# 1_Main_copy.net
KiCad netlist of a schematic drawn in Altium Designer
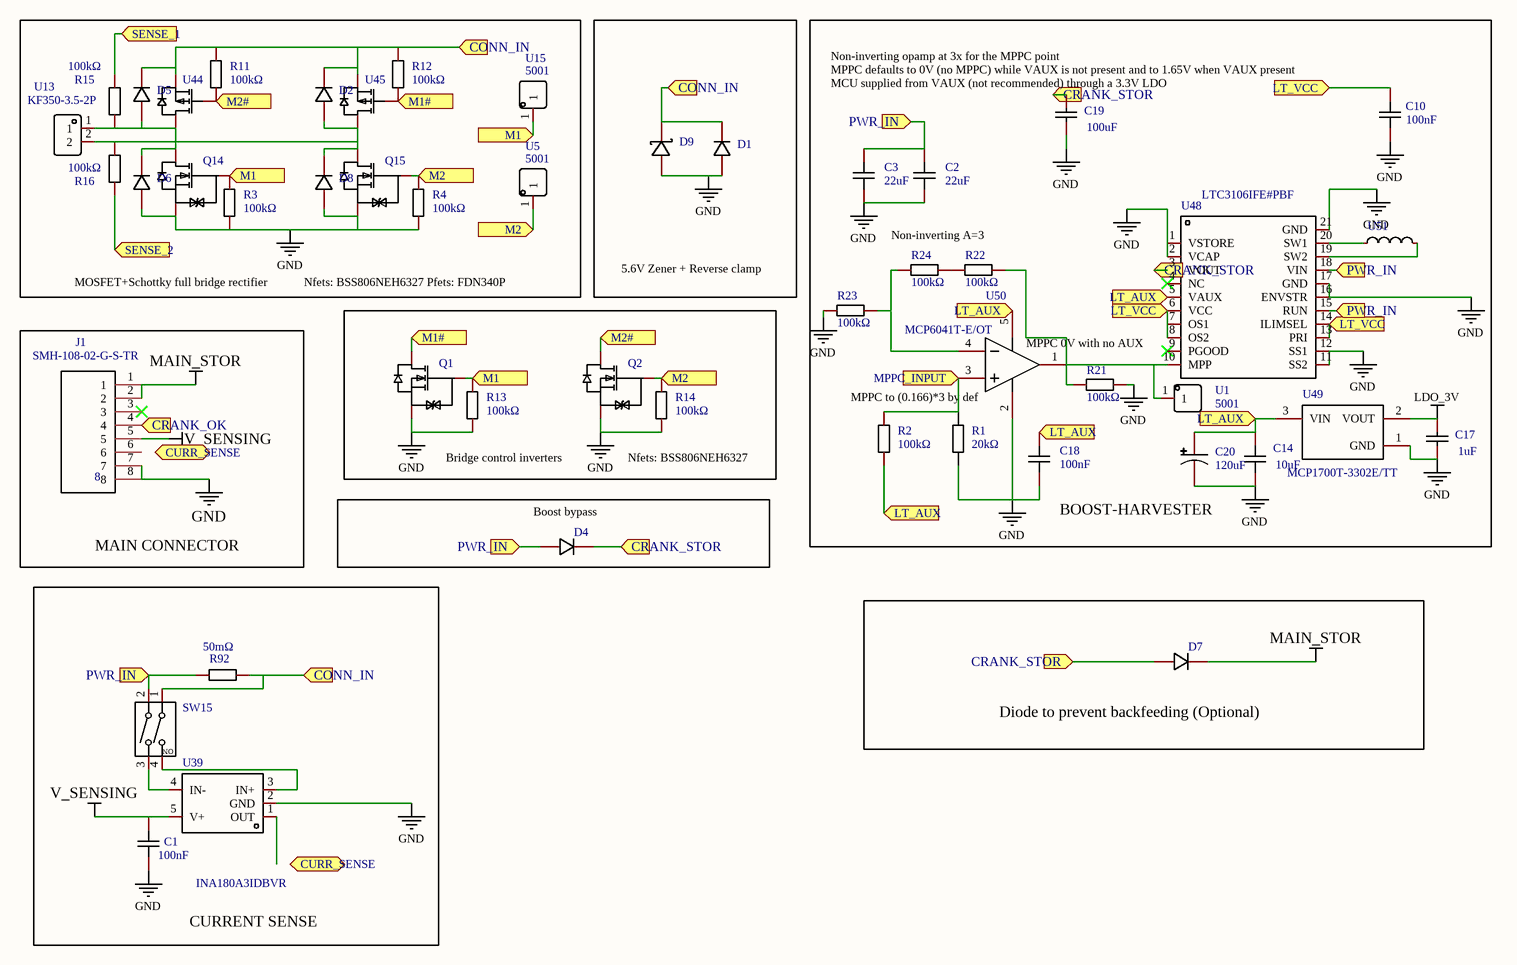
[diagram p0: 1_Main copy.schdoc]

(export (version "E")
  (design (tool "Eeschema 10.0.6"))
  (components
    (comp (ref "C1")
      (value "100nF")
      (fields
        (field (name "NAME") "100nF")
        (field (name "MANUFACTURER") "YAGEO")
        (field (name "MANUFACTURER PART") "CC0603KRX7R9BB104")
      )
      (libsource (lib "altium-import") (part "root_1_CC0603KRX7R9BB104_"))
    )
    (comp (ref "C2")
      (value "22uF")
      (fields
        (field (name "MANUFACTURER") "SAMSUNG(三星)")
        (field (name "MANUFACTURER PART") "CL21A226MAQNNNE")
        (field (name "TOLERANCE") "±20%")
      )
      (libsource (lib "altium-import") (part "root_1_mirrored_CL21A226MAQNNNE_C45783_"))
    )
    (comp (ref "C3")
      (value "22uF")
      (fields
        (field (name "MANUFACTURER") "SAMSUNG(三星)")
        (field (name "MANUFACTURER PART") "CL21A226MAQNNNE")
        (field (name "TOLERANCE") "±20%")
      )
      (libsource (lib "altium-import") (part "root_1_mirrored_CL21A226MAQNNNE_C45783_"))
    )
    (comp (ref "C10")
      (value "100nF")
      (fields
        (field (name "NAME") "100nF")
        (field (name "MANUFACTURER") "YAGEO")
        (field (name "MANUFACTURER PART") "CC0603KRX7R9BB104")
      )
      (libsource (lib "altium-import") (part "root_3_CC0603KRX7R9BB104_"))
    )
    (comp (ref "C14")
      (value "10uF")
      (fields
        (field (name "MANUFACTURER") "SAMSUNG(三星)")
        (field (name "MANUFACTURER PART") "CL10A106MA8NRNC")
        (field (name "TOLERANCE") "±20%")
      )
      (libsource (lib "altium-import") (part "root_1_CL10A106MA8NRNC_"))
    )
    (comp (ref "C17")
      (value "1uF")
      (fields
        (field (name "MANUFACTURER") "SAMSUNG(三星)")
        (field (name "MANUFACTURER PART") "CL10A105KB8NNNC")
        (field (name "TOLERANCE") "±10%")
      )
      (libsource (lib "altium-import") (part "root_1_CL10A105KB8NNNC_"))
    )
    (comp (ref "C18")
      (value "100nF")
      (fields
        (field (name "NAME") "100nF")
        (field (name "MANUFACTURER") "YAGEO")
        (field (name "MANUFACTURER PART") "CC0603KRX7R9BB104")
      )
      (libsource (lib "altium-import") (part "root_1_CC0603KRX7R9BB104_"))
    )
    (comp (ref "C19")
      (value "100uF")
      (fields
        (field (name "MANUFACTURER") "SAMSUNG(三星)")
        (field (name "MANUFACTURER PART") "CL32A107MQVNNNE")
        (field (name "TOLERANCE") "±20%")
      )
      (libsource (lib "altium-import") (part "root_1_CL32A107MQVNNNE_"))
    )
    (comp (ref "C20")
      (value "120uF")
      (fields
        (field (name "MANUFACTURER") "PANASONIC(松下)")
        (field (name "MANUFACTURER PART") "EEEFK1A121SR")
        (field (name "TOLERANCE") "±20%")
      )
      (libsource (lib "altium-import") (part "root_0_EEEFK1A121SR_"))
    )
    (comp (ref "D1")
      (value "STPS1L30U")
      (description "Reverse Voltage (Vr):30V Average Rectified Current (Io):1A Forward Voltage (Vf@If):395mV@1A")
      (fields (field (name "MANUFACTURER") "ST(意法半导体)"))
      (libsource (lib "altium-import") (part "root_3_STPS1L30U_"))
    )
    (comp (ref "D2")
      (value "STPS1L30U")
      (description "Reverse Voltage (Vr):30V Average Rectified Current (Io):1A Forward Voltage (Vf@If):395mV@1A")
      (fields (field (name "MANUFACTURER") "ST(意法半导体)"))
      (libsource (lib "altium-import") (part "root_3_STPS1L30U_"))
    )
    (comp (ref "D4")
      (value "STPS1L30U")
      (description "Reverse Voltage (Vr):30V Average Rectified Current (Io):1A Forward Voltage (Vf@If):395mV@1A")
      (fields (field (name "MANUFACTURER") "ST(意法半导体)"))
      (libsource (lib "altium-import") (part "root_2_STPS1L30U_"))
    )
    (comp (ref "D5")
      (value "STPS1L30U")
      (description "Reverse Voltage (Vr):30V Average Rectified Current (Io):1A Forward Voltage (Vf@If):395mV@1A")
      (fields (field (name "MANUFACTURER") "ST(意法半导体)"))
      (libsource (lib "altium-import") (part "root_3_STPS1L30U_"))
    )
    (comp (ref "D6")
      (value "STPS1L30U")
      (description "Reverse Voltage (Vr):30V Average Rectified Current (Io):1A Forward Voltage (Vf@If):395mV@1A")
      (fields (field (name "MANUFACTURER") "ST(意法半导体)"))
      (libsource (lib "altium-import") (part "root_3_STPS1L30U_"))
    )
    (comp (ref "D7")
      (value "STPS1L30U")
      (description "Reverse Voltage (Vr):30V Average Rectified Current (Io):1A Forward Voltage (Vf@If):395mV@1A")
      (fields (field (name "MANUFACTURER") "ST(意法半导体)"))
      (libsource (lib "altium-import") (part "root_2_STPS1L30U_"))
    )
    (comp (ref "D8")
      (value "STPS1L30U")
      (description "Reverse Voltage (Vr):30V Average Rectified Current (Io):1A Forward Voltage (Vf@If):395mV@1A")
      (fields (field (name "MANUFACTURER") "ST(意法半导体)"))
      (libsource (lib "altium-import") (part "root_3_STPS1L30U_"))
    )
    (comp (ref "D9")
      (value "SMAZ5V6-13-F")
      (fields (field (name "MANUFACTURER") "DIODES(美台)") (field (name "TOLERANCE") "±5%"))
      (libsource (lib "altium-import") (part "root_3_SMAZ5V6-13-F_"))
    )
    (comp (ref "J1")
      (value "SMH-108-02-G-S-TR")
      (fields (field (name "NAME") "SMH-108-02-G-S-TR") (field (name "NAME_1") "8"))
      (libsource (lib "altium-import") (part "root_0_SMH-108-02-G-S-TR_"))
    )
    (comp (ref "Q1")
      (value "BSS806NEH6327")
      (fields (field (name "MANUFACTURER") "Infineon(英飞凌)"))
      (libsource (lib "altium-import") (part "root_0_mirrored_BSS806NEH6327_"))
    )
    (comp (ref "Q2")
      (value "BSS806NEH6327")
      (fields (field (name "MANUFACTURER") "Infineon(英飞凌)"))
      (libsource (lib "altium-import") (part "root_0_mirrored_BSS806NEH6327_"))
    )
    (comp (ref "Q14")
      (value "BSS806NEH6327")
      (fields (field (name "MANUFACTURER") "Infineon(英飞凌)"))
      (libsource (lib "altium-import") (part "root_0_mirrored_BSS806NEH6327_"))
    )
    (comp (ref "Q15")
      (value "BSS806NEH6327")
      (fields (field (name "MANUFACTURER") "Infineon(英飞凌)"))
      (libsource (lib "altium-import") (part "root_0_mirrored_BSS806NEH6327_"))
    )
    (comp (ref "R1")
      (value "20kΩ")
      (fields
        (field (name "NAME") "20kΩ")
        (field (name "MANUFACTURER") "UniOhm")
        (field (name "MANUFACTURER PART") "0603WAF2002T5E")
      )
      (libsource (lib "altium-import") (part "root_3_0603WAF2002T5E_"))
    )
    (comp (ref "R2")
      (value "100kΩ")
      (fields
        (field (name "MANUFACTURER") "UNI-ROYAL(厚声)")
        (field (name "MANUFACTURER PART") "0603WAF1003T5E")
        (field (name "TOLERANCE") "±1%")
      )
      (libsource (lib "altium-import") (part "root_3_0603WAF1003T5E_"))
    )
    (comp (ref "R3")
      (value "100kΩ")
      (fields
        (field (name "MANUFACTURER") "UNI-ROYAL(厚声)")
        (field (name "MANUFACTURER PART") "0603WAF1003T5E")
        (field (name "TOLERANCE") "±1%")
      )
      (libsource (lib "altium-import") (part "root_1_0603WAF1003T5E_"))
    )
    (comp (ref "R4")
      (value "100kΩ")
      (fields
        (field (name "MANUFACTURER") "UNI-ROYAL(厚声)")
        (field (name "MANUFACTURER PART") "0603WAF1003T5E")
        (field (name "TOLERANCE") "±1%")
      )
      (libsource (lib "altium-import") (part "root_1_0603WAF1003T5E_"))
    )
    (comp (ref "R11")
      (value "100kΩ")
      (fields
        (field (name "MANUFACTURER") "UNI-ROYAL(厚声)")
        (field (name "MANUFACTURER PART") "0603WAF1003T5E")
        (field (name "TOLERANCE") "±1%")
      )
      (libsource (lib "altium-import") (part "root_1_0603WAF1003T5E_"))
    )
    (comp (ref "R12")
      (value "100kΩ")
      (fields
        (field (name "MANUFACTURER") "UNI-ROYAL(厚声)")
        (field (name "MANUFACTURER PART") "0603WAF1003T5E")
        (field (name "TOLERANCE") "±1%")
      )
      (libsource (lib "altium-import") (part "root_1_0603WAF1003T5E_"))
    )
    (comp (ref "R13")
      (value "100kΩ")
      (fields
        (field (name "MANUFACTURER") "UNI-ROYAL(厚声)")
        (field (name "MANUFACTURER PART") "0603WAF1003T5E")
        (field (name "TOLERANCE") "±1%")
      )
      (libsource (lib "altium-import") (part "root_1_0603WAF1003T5E_"))
    )
    (comp (ref "R14")
      (value "100kΩ")
      (fields
        (field (name "MANUFACTURER") "UNI-ROYAL(厚声)")
        (field (name "MANUFACTURER PART") "0603WAF1003T5E")
        (field (name "TOLERANCE") "±1%")
      )
      (libsource (lib "altium-import") (part "root_1_0603WAF1003T5E_"))
    )
    (comp (ref "R15")
      (value "100kΩ")
      (fields
        (field (name "MANUFACTURER") "UNI-ROYAL(厚声)")
        (field (name "MANUFACTURER PART") "0603WAF1003T5E")
        (field (name "TOLERANCE") "±1%")
      )
      (libsource (lib "altium-import") (part "root_1_0603WAF1003T5E_"))
    )
    (comp (ref "R16")
      (value "100kΩ")
      (fields
        (field (name "MANUFACTURER") "UNI-ROYAL(厚声)")
        (field (name "MANUFACTURER PART") "0603WAF1003T5E")
        (field (name "TOLERANCE") "±1%")
      )
      (libsource (lib "altium-import") (part "root_1_0603WAF1003T5E_"))
    )
    (comp (ref "R21")
      (value "100kΩ")
      (fields
        (field (name "MANUFACTURER") "UNI-ROYAL(厚声)")
        (field (name "MANUFACTURER PART") "0603WAF1003T5E")
        (field (name "TOLERANCE") "±1%")
      )
      (libsource (lib "altium-import") (part "root_0_0603WAF1003T5E_"))
    )
    (comp (ref "R22")
      (value "100kΩ")
      (fields
        (field (name "MANUFACTURER") "UNI-ROYAL(厚声)")
        (field (name "MANUFACTURER PART") "0603WAF1003T5E")
        (field (name "TOLERANCE") "±1%")
      )
      (libsource (lib "altium-import") (part "root_2_0603WAF1003T5E_"))
    )
    (comp (ref "R23")
      (value "100kΩ")
      (fields
        (field (name "MANUFACTURER") "UNI-ROYAL(厚声)")
        (field (name "MANUFACTURER PART") "0603WAF1003T5E")
        (field (name "TOLERANCE") "±1%")
      )
      (libsource (lib "altium-import") (part "root_2_0603WAF1003T5E_"))
    )
    (comp (ref "R24")
      (value "100kΩ")
      (fields
        (field (name "MANUFACTURER") "UNI-ROYAL(厚声)")
        (field (name "MANUFACTURER PART") "0603WAF1003T5E")
        (field (name "TOLERANCE") "±1%")
      )
      (libsource (lib "altium-import") (part "root_2_0603WAF1003T5E_"))
    )
    (comp (ref "R92")
      (value "50mΩ")
      (fields
        (field (name "MANUFACTURER") "UNI-ROYAL(厚声)")
        (field (name "MANUFACTURER PART") "1206W3F500MT5E")
        (field (name "TOLERANCE") "±1%")
      )
      (libsource (lib "altium-import") (part "root_0_1206W3F500MT5E_C127691_"))
    )
    (comp (ref "SW15")
      (value "A6S-2102-PH")
      (fields (field (name "MANUFACTURER") "OMRON(欧姆龙)"))
      (libsource (lib "altium-import") (part "root_2_A6S-2102-PH_"))
    )
    (comp (ref "U1")
      (value "5001")
      (fields (field (name "NAME") "5001") (field (name "MANUFACTURER") "Keystone"))
      (libsource (lib "altium-import") (part "root_0_5001_"))
    )
    (comp (ref "U5")
      (value "5001")
      (fields (field (name "NAME") "5001") (field (name "MANUFACTURER") "Keystone"))
      (libsource (lib "altium-import") (part "root_1_5001_"))
    )
    (comp (ref "U13")
      (value "KF350-3.5-2P")
      (fields (field (name "NAME") "KF350-3.5-2P") (field (name "MANUFACTURER") "Cixi Kefa Elec"))
      (libsource (lib "altium-import") (part "root_2_KF350-3.5-2P_"))
    )
    (comp (ref "U15")
      (value "5001")
      (fields (field (name "NAME") "5001") (field (name "MANUFACTURER") "Keystone"))
      (libsource (lib "altium-import") (part "root_1_5001_"))
    )
    (comp (ref "U39")
      (value "INA180A3IDBVR")
      (fields (field (name "LCSC PART NAME") "INA180A3IDBVR") (field (name "MANUFACTURER") "TI(德州仪器)"))
      (libsource (lib "altium-import") (part "root_2_INA180A3IDBVR_"))
    )
    (comp (ref "U44")
      (value "FDN340P")
      (fields (field (name "MANUFACTURER") "onsemi(安森美)"))
      (libsource (lib "altium-import") (part "root_2_FDN340P_C3277832_"))
    )
    (comp (ref "U45")
      (value "FDN340P")
      (fields (field (name "MANUFACTURER") "onsemi(安森美)"))
      (libsource (lib "altium-import") (part "root_2_FDN340P_C3277832_"))
    )
    (comp (ref "U48")
      (value "LTC3106IFE#PBF")
      (fields
        (field (name "MANUFACTURER") "ADI(亚德诺)/LINEAR(凌特)")
        (field (name "MANUFACTURER PART") "LTC3106IFE#PBF")
      )
      (libsource (lib "altium-import") (part "root_0_LTC3106IFE#PBF_"))
    )
    (comp (ref "U49")
      (value "MCP1700T-3302E/TT")
      (fields (field (name "DEVICE") "MCP1700T-3302E/TT") (field (name "MANUFACTURER") "MICROCHIP(美国微芯)"))
      (libsource (lib "altium-import") (part "root_0_MCP1700T-3302E/TT_"))
    )
    (comp (ref "U50")
      (value "MCP6041T-E/OT")
      (fields
        (field (name "MANUFACTURER") "MICROCHIP(美国微芯)")
        (field (name "MANUFACTURER PART") "MCP6041T-E/OT")
      )
      (libsource (lib "altium-import") (part "root_0_MCP6041T-E/OT_"))
    )
    (comp (ref "U51") (value "Ind-LPS4018") (libsource (lib "altium-import") (part "root_0_Ind-LPS4018_")))
  )
  (nets
    (net (code "1") (name "/CONN_IN") (class "Default")
      (node (ref "D1") (pin "1") (pinfunction "1_1") (pintype "passive"))
      (node (ref "D2") (pin "1") (pinfunction "1_1") (pintype "passive"))
      (node (ref "D5") (pin "1") (pinfunction "1_1") (pintype "passive"))
      (node (ref "D9") (pin "1") (pinfunction "C_1") (pintype "passive"))
      (node (ref "R11") (pin "2") (pinfunction "2_2") (pintype "passive"))
      (node (ref "R12") (pin "2") (pinfunction "2_2") (pintype "passive"))
      (node (ref "R92") (pin "2") (pinfunction "2_2") (pintype "passive"))
      (node (ref "SW15") (pin "1") (pinfunction "1_1") (pintype "passive"))
      (node (ref "U44") (pin "2") (pinfunction "S_2") (pintype "passive"))
      (node (ref "U45") (pin "2") (pinfunction "S_2") (pintype "passive"))
    )
    (net (code "2") (name "/CRANK_OK") (class "Default")
      (node (ref "J1") (pin "4") (pinfunction "4_4") (pintype "passive"))
    )
    (net (code "3") (name "/CRANK_STOR") (class "Default")
      (node (ref "C19") (pin "2") (pinfunction "2_2") (pintype "passive"))
      (node (ref "D4") (pin "1") (pinfunction "1_1") (pintype "passive"))
      (node (ref "D7") (pin "2") (pinfunction "2_2") (pintype "passive"))
      (node (ref "U48") (pin "3") (pinfunction "VOUT_3") (pintype "passive"))
    )
    (net (code "5") (name "/LT_AUX") (class "Default")
      (node (ref "C14") (pin "2") (pinfunction "2_2") (pintype "passive"))
      (node (ref "C18") (pin "2") (pinfunction "2_2") (pintype "passive"))
      (node (ref "C20") (pin "1") (pinfunction "1_1") (pintype "passive"))
      (node (ref "R2") (pin "2") (pinfunction "2_2") (pintype "passive"))
      (node (ref "U48") (pin "5") (pinfunction "VAUX_5") (pintype "passive"))
      (node (ref "U49") (pin "3") (pinfunction "VIN_3") (pintype "passive"))
      (node (ref "U50") (pin "5") (pinfunction "VDD_5") (pintype "passive"))
    )
    (net (code "6") (name "/LT_VCC") (class "Default")
      (node (ref "C10") (pin "1") (pinfunction "1_1") (pintype "passive"))
      (node (ref "U48") (pin "13") (pinfunction "PRI_13") (pintype "passive"))
      (node (ref "U48") (pin "14") (pinfunction "ILIMSEL_14") (pintype "passive"))
      (node (ref "U48") (pin "6") (pinfunction "VCC_6") (pintype "passive"))
      (node (ref "U48") (pin "7") (pinfunction "OS1_7") (pintype "passive"))
      (node (ref "U48") (pin "8") (pinfunction "OS2_8") (pintype "passive"))
    )
    (net (code "7") (name "/M1") (class "Default")
      (node (ref "Q1") (pin "1") (pinfunction "G_1") (pintype "passive"))
      (node (ref "Q14") (pin "1") (pinfunction "G_1") (pintype "passive"))
      (node (ref "R13") (pin "2") (pinfunction "2_2") (pintype "passive"))
      (node (ref "R3") (pin "2") (pinfunction "2_2") (pintype "passive"))
      (node (ref "U15") (pin "1") (pinfunction "1_1") (pintype "passive"))
    )
    (net (code "8") (name "/M1#") (class "Default")
      (node (ref "Q1") (pin "3") (pinfunction "D_3") (pintype "passive"))
      (node (ref "R12") (pin "1") (pinfunction "1_1") (pintype "passive"))
      (node (ref "U45") (pin "1") (pinfunction "G_1") (pintype "passive"))
    )
    (net (code "9") (name "/M2") (class "Default")
      (node (ref "Q15") (pin "1") (pinfunction "G_1") (pintype "passive"))
      (node (ref "Q2") (pin "1") (pinfunction "G_1") (pintype "passive"))
      (node (ref "R14") (pin "2") (pinfunction "2_2") (pintype "passive"))
      (node (ref "R4") (pin "2") (pinfunction "2_2") (pintype "passive"))
      (node (ref "U5") (pin "1") (pinfunction "1_1") (pintype "passive"))
    )
    (net (code "10") (name "/M2#") (class "Default")
      (node (ref "Q2") (pin "3") (pinfunction "D_3") (pintype "passive"))
      (node (ref "R11") (pin "1") (pinfunction "1_1") (pintype "passive"))
      (node (ref "U44") (pin "1") (pinfunction "G_1") (pintype "passive"))
    )
    (net (code "11") (name "/MPPC_INPUT") (class "Default")
      (node (ref "R1") (pin "1") (pinfunction "1_1") (pintype "passive"))
      (node (ref "R2") (pin "1") (pinfunction "1_1") (pintype "passive"))
      (node (ref "U50") (pin "3") (pinfunction "VIN+_3") (pintype "passive"))
    )
    (net (code "12") (name "/PWR_IN") (class "Default")
      (node (ref "C2") (pin "2") (pinfunction "2_2") (pintype "passive"))
      (node (ref "C3") (pin "2") (pinfunction "2_2") (pintype "passive"))
      (node (ref "D4") (pin "2") (pinfunction "2_2") (pintype "passive"))
      (node (ref "R92") (pin "1") (pinfunction "1_1") (pintype "passive"))
      (node (ref "SW15") (pin "2") (pinfunction "2_2") (pintype "passive"))
      (node (ref "U48") (pin "15") (pinfunction "RUN_15") (pintype "passive"))
      (node (ref "U48") (pin "18") (pinfunction "VIN_18") (pintype "passive"))
    )
    (net (code "13") (name "/SENSE_1") (class "Default")
      (node (ref "R15") (pin "2") (pinfunction "2_2") (pintype "passive"))
    )
    (net (code "14") (name "/SENSE_2") (class "Default")
      (node (ref "R16") (pin "1") (pinfunction "1_1") (pintype "passive"))
    )
    (net (code "15") (name "GND") (class "Default")
      (node (ref "C1") (pin "1") (pinfunction "1_1") (pintype "passive"))
      (node (ref "C10") (pin "2") (pinfunction "2_2") (pintype "passive"))
      (node (ref "C14") (pin "1") (pinfunction "1_1") (pintype "passive"))
      (node (ref "C17") (pin "1") (pinfunction "1_1") (pintype "passive"))
      (node (ref "C18") (pin "1") (pinfunction "1_1") (pintype "passive"))
      (node (ref "C19") (pin "1") (pinfunction "1_1") (pintype "passive"))
      (node (ref "C2") (pin "1") (pinfunction "1_1") (pintype "passive"))
      (node (ref "C20") (pin "2") (pinfunction "2_2") (pintype "passive"))
      (node (ref "C3") (pin "1") (pinfunction "1_1") (pintype "passive"))
      (node (ref "D1") (pin "2") (pinfunction "2_2") (pintype "passive"))
      (node (ref "D6") (pin "2") (pinfunction "2_2") (pintype "passive"))
      (node (ref "D8") (pin "2") (pinfunction "2_2") (pintype "passive"))
      (node (ref "D9") (pin "2") (pinfunction "A_2") (pintype "passive"))
      (node (ref "J1") (pin "7") (pinfunction "7_7") (pintype "passive"))
      (node (ref "J1") (pin "8") (pinfunction "8_8") (pintype "passive"))
      (node (ref "Q1") (pin "2") (pinfunction "S_2") (pintype "passive"))
      (node (ref "Q14") (pin "2") (pinfunction "S_2") (pintype "passive"))
      (node (ref "Q15") (pin "2") (pinfunction "S_2") (pintype "passive"))
      (node (ref "Q2") (pin "2") (pinfunction "S_2") (pintype "passive"))
      (node (ref "R1") (pin "2") (pinfunction "2_2") (pintype "passive"))
      (node (ref "R13") (pin "1") (pinfunction "1_1") (pintype "passive"))
      (node (ref "R14") (pin "1") (pinfunction "1_1") (pintype "passive"))
      (node (ref "R21") (pin "2") (pinfunction "2_2") (pintype "passive"))
      (node (ref "R23") (pin "2") (pinfunction "2_2") (pintype "passive"))
      (node (ref "R3") (pin "1") (pinfunction "1_1") (pintype "passive"))
      (node (ref "R4") (pin "1") (pinfunction "1_1") (pintype "passive"))
      (node (ref "U39") (pin "2") (pinfunction "GND_2") (pintype "passive"))
      (node (ref "U48") (pin "1") (pinfunction "VSTORE_1") (pintype "passive"))
      (node (ref "U48") (pin "11") (pinfunction "SS2_11") (pintype "passive"))
      (node (ref "U48") (pin "12") (pinfunction "SS1_12") (pintype "passive"))
      (node (ref "U48") (pin "16") (pinfunction "ENVSTR_16") (pintype "passive"))
      (node (ref "U48") (pin "17") (pinfunction "GND_17") (pintype "passive"))
      (node (ref "U48") (pin "2") (pinfunction "VCAP_2") (pintype "passive"))
      (node (ref "U48") (pin "21") (pinfunction "GND_21") (pintype "passive"))
      (node (ref "U49") (pin "1") (pinfunction "GND_1") (pintype "passive"))
      (node (ref "U50") (pin "2") (pinfunction "VSS_2") (pintype "passive"))
    )
    (net (code "16") (name "LDO_3V") (class "Default")
      (node (ref "C17") (pin "2") (pinfunction "2_2") (pintype "passive"))
      (node (ref "U49") (pin "2") (pinfunction "VOUT_2") (pintype "passive"))
    )
    (net (code "17") (name "MAIN_STOR") (class "Default")
      (node (ref "D7") (pin "1") (pinfunction "1_1") (pintype "passive"))
      (node (ref "J1") (pin "1") (pinfunction "1_1") (pintype "passive"))
      (node (ref "J1") (pin "2") (pinfunction "2_2") (pintype "passive"))
    )
    (net (code "18") (name "Net-(Q14-D)") (class "Default")
      (node (ref "D5") (pin "2") (pinfunction "2_2") (pintype "passive"))
      (node (ref "D6") (pin "1") (pinfunction "1_1") (pintype "passive"))
      (node (ref "Q14") (pin "3") (pinfunction "D_3") (pintype "passive"))
      (node (ref "R15") (pin "1") (pinfunction "1_1") (pintype "passive"))
      (node (ref "U13") (pin "1") (pinfunction "1_1") (pintype "passive"))
      (node (ref "U44") (pin "3") (pinfunction "D_3") (pintype "passive"))
    )
    (net (code "19") (name "Net-(Q15-D)") (class "Default")
      (node (ref "D2") (pin "2") (pinfunction "2_2") (pintype "passive"))
      (node (ref "D8") (pin "1") (pinfunction "1_1") (pintype "passive"))
      (node (ref "Q15") (pin "3") (pinfunction "D_3") (pintype "passive"))
      (node (ref "R16") (pin "2") (pinfunction "2_2") (pintype "passive"))
      (node (ref "U13") (pin "2") (pinfunction "2_2") (pintype "passive"))
      (node (ref "U45") (pin "3") (pinfunction "D_3") (pintype "passive"))
    )
    (net (code "20") (name "Net-(R22-Pad2)") (class "Default")
      (node (ref "R22") (pin "2") (pinfunction "2_2") (pintype "passive"))
      (node (ref "R24") (pin "1") (pinfunction "1_1") (pintype "passive"))
    )
    (net (code "21") (name "Net-(U39-IN+)") (class "Default")
      (node (ref "SW15") (pin "4") (pinfunction "4_4") (pintype "passive"))
      (node (ref "U39") (pin "3") (pinfunction "IN+_3") (pintype "passive"))
    )
    (net (code "22") (name "Net-(U39-IN-)") (class "Default")
      (node (ref "SW15") (pin "3") (pinfunction "3_3") (pintype "passive"))
      (node (ref "U39") (pin "4") (pinfunction "IN-_4") (pintype "passive"))
    )
    (net (code "23") (name "Net-(U48-MPP)") (class "Default")
      (node (ref "R21") (pin "1") (pinfunction "1_1") (pintype "passive"))
      (node (ref "R22") (pin "1") (pinfunction "1_1") (pintype "passive"))
      (node (ref "U1") (pin "1") (pinfunction "1_1") (pintype "passive"))
      (node (ref "U48") (pin "10") (pinfunction "MPP_10") (pintype "passive"))
      (node (ref "U50") (pin "1") (pinfunction "VOUT_1") (pintype "passive"))
    )
    (net (code "24") (name "Net-(U48-SW1)") (class "Default")
      (node (ref "U48") (pin "20") (pinfunction "SW1_20") (pintype "passive"))
      (node (ref "U51") (pin "1") (pinfunction "1_1") (pintype "passive"))
    )
    (net (code "25") (name "Net-(U48-SW2)") (class "Default")
      (node (ref "U48") (pin "19") (pinfunction "SW2_19") (pintype "passive"))
      (node (ref "U51") (pin "2") (pinfunction "2_2") (pintype "passive"))
    )
    (net (code "26") (name "Net-(U50-VIN-)") (class "Default")
      (node (ref "R23") (pin "1") (pinfunction "1_1") (pintype "passive"))
      (node (ref "R24") (pin "2") (pinfunction "2_2") (pintype "passive"))
      (node (ref "U50") (pin "4") (pinfunction "VIN-_4") (pintype "passive"))
    )
    (net (code "27") (name "V_SENSING") (class "Default")
      (node (ref "C1") (pin "2") (pinfunction "2_2") (pintype "passive"))
      (node (ref "J1") (pin "5") (pinfunction "5_5") (pintype "passive"))
      (node (ref "U39") (pin "5") (pinfunction "V+_5") (pintype "passive"))
    )
    (net (code "28") (name "unconnected-(J1-Pad3)") (class "Default")
      (node (ref "J1") (pin "3") (pinfunction "3_3") (pintype "passive+no_connect"))
    )
    (net (code "29") (name "unconnected-(J1-Pad6)") (class "Default")
      (node (ref "J1") (pin "6") (pinfunction "6_6") (pintype "passive"))
    )
    (net (code "30") (name "unconnected-(U39-OUT-Pad1)") (class "Default")
      (node (ref "U39") (pin "1") (pinfunction "OUT_1") (pintype "passive"))
    )
    (net (code "31") (name "unconnected-(U48-NC-Pad4)") (class "Default")
      (node (ref "U48") (pin "4") (pinfunction "NC_4") (pintype "passive+no_connect"))
    )
    (net (code "32") (name "unconnected-(U48-PGOOD-Pad9)") (class "Default")
      (node (ref "U48") (pin "9") (pinfunction "PGOOD_9") (pintype "passive+no_connect"))
    )
  )
)
